# 06_-_POWER.net
KiCad netlist of a schematic drawn in Altium Designer
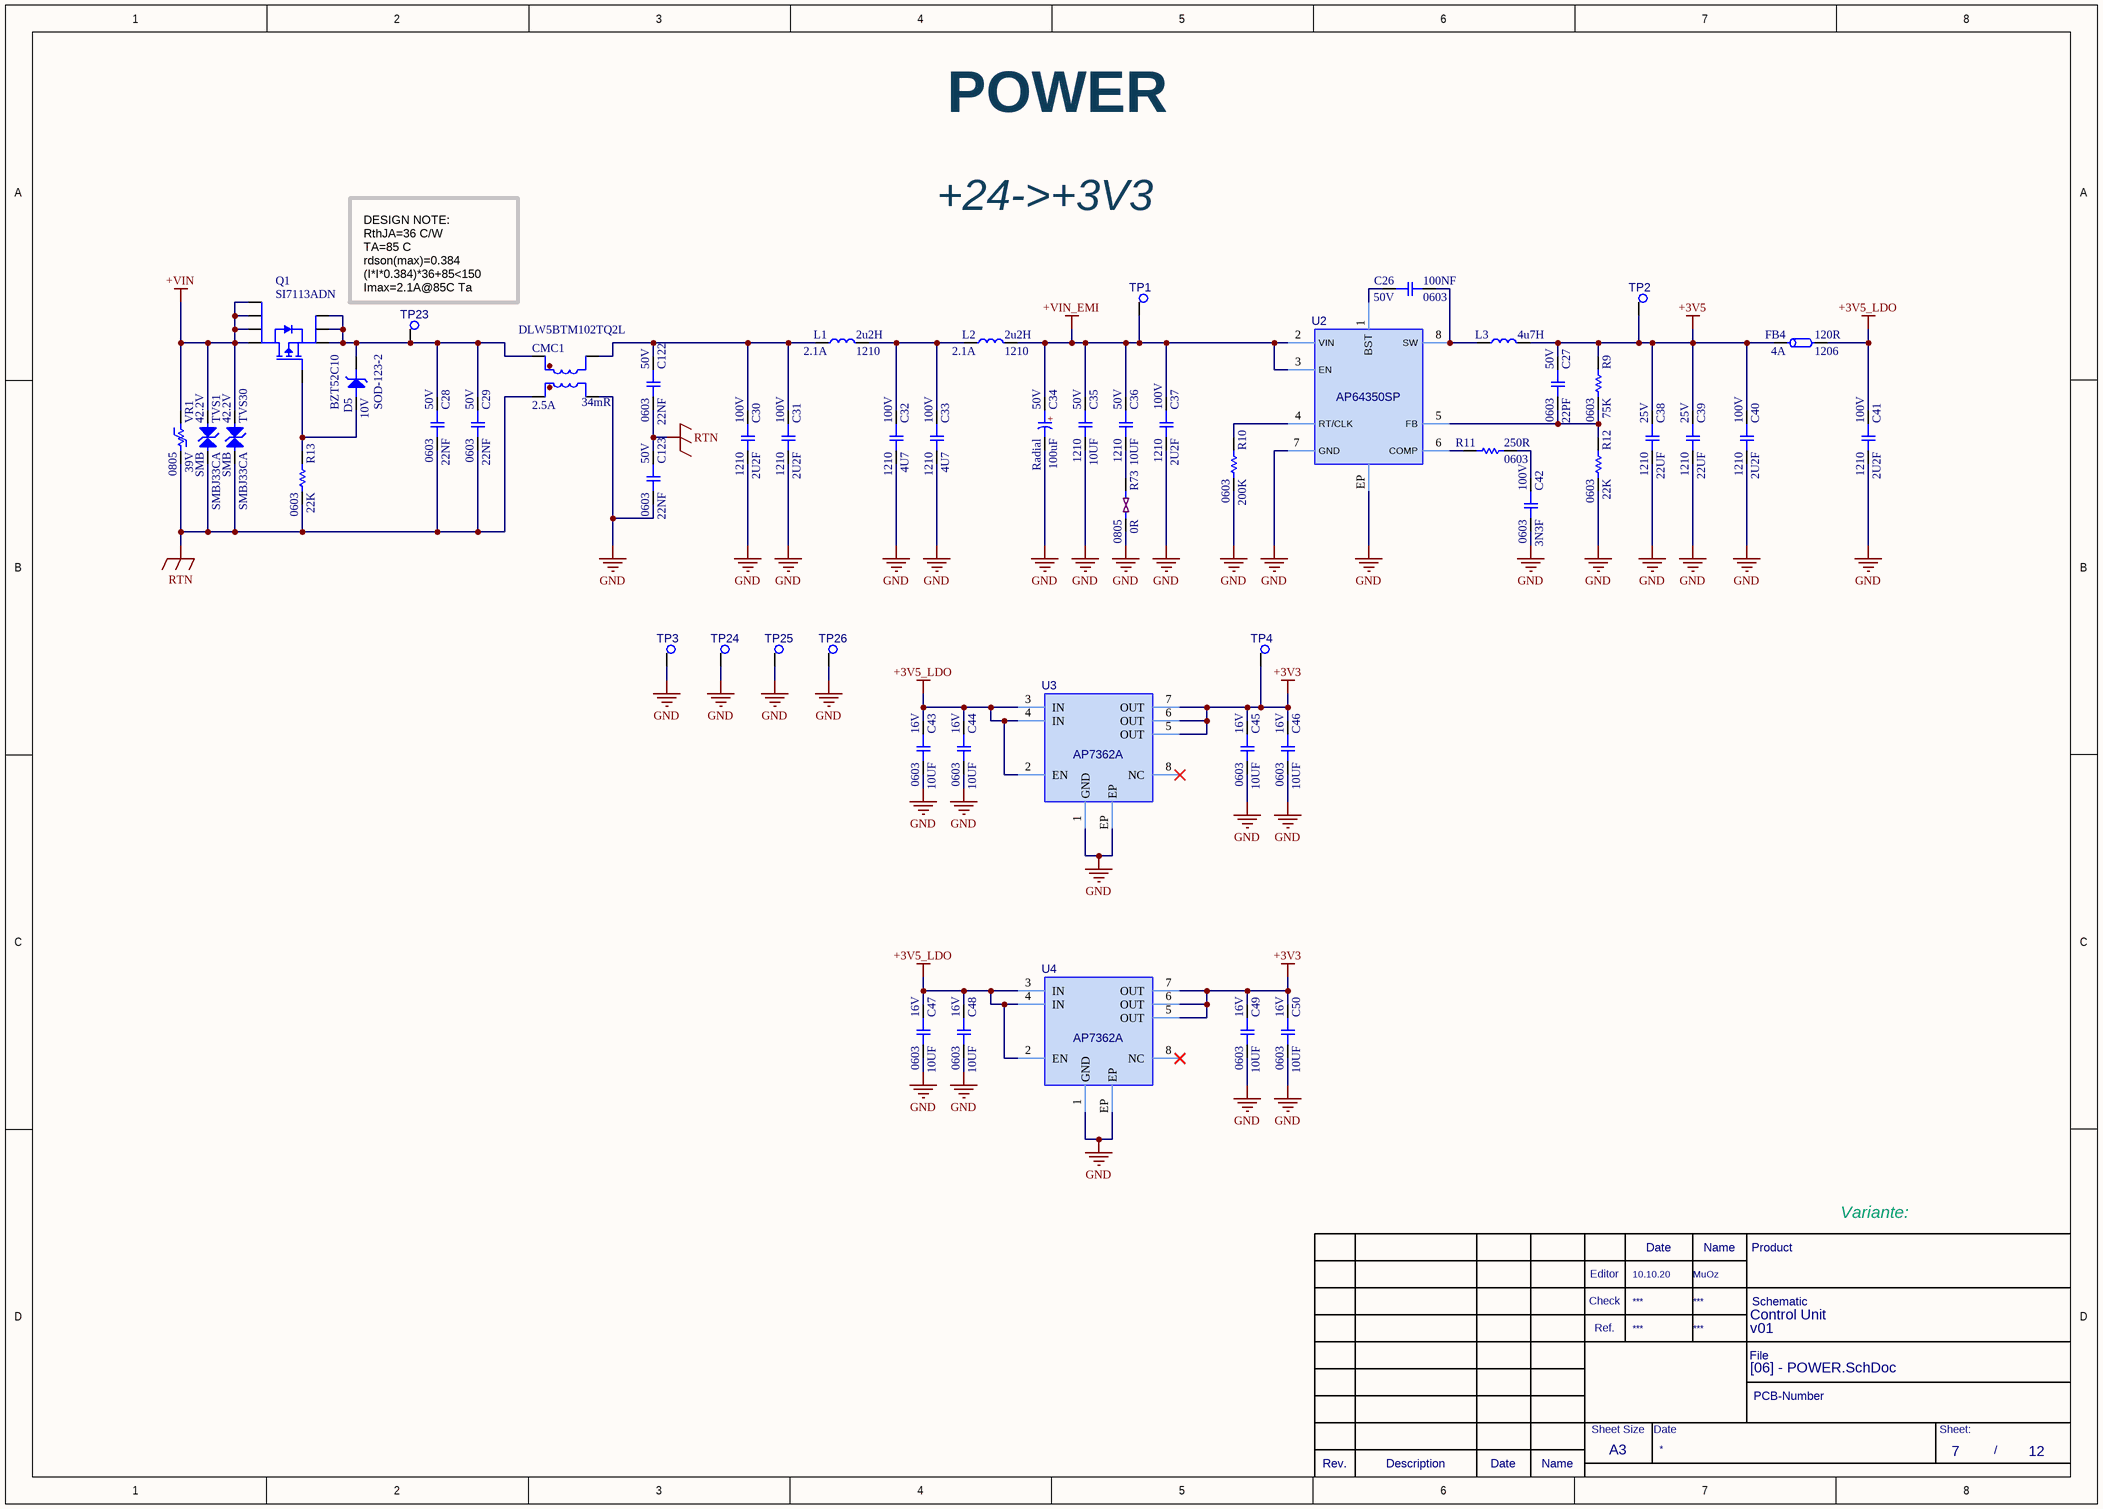
[diagram p0: [06] - POWER.SchDoc]

(export (version "E")
  (design (tool "Eeschema 10.0.6"))
  (components
    (comp (ref "C26")
      (value "100NF")
      (footprint "C-0603")
      (description "CAP CER 0.1UF 50V X7R 0603")
      (fields
        (field (name "MANUFACTURER") "TDK")
        (field (name "MANUFACTURER PART NUMBER") "C1608X7R1H104K080AA")
        (field (name "VOLTAGE RATING") "50V")
        (field (name "CASE CODE (IMPERIAL)") "0603")
        (field (name ".CREATOR") "F:TALI")
      )
      (libsource (lib "BARKO_SCHLIB") (part "C-100NF-0603"))
    )
    (comp (ref "C27")
      (value "22PF")
      (footprint "C-0603")
      (description "CAP CER 22PF 50V C0G/NP0 0603")
      (fields
        (field (name "MANUFACTURER") "Samsung")
        (field (name "MANUFACTURER PART NUMBER") "CL10C220JB8NNNC")
        (field (name "VOLTAGE RATING") "50V")
        (field (name "CASE/PACKAGE") "0603")
        (field (name ".CREATOR") "F:TALI")
      )
      (libsource (lib "BARKO_SCHLIB") (part "C-22PF-0603"))
    )
    (comp (ref "C28")
      (value "22NF")
      (footprint "C-0603")
      (description "CAP CER 0.022UF 50V X7R 0603L")
      (fields
        (field (name "MANUFACTURER") "Yageo")
        (field (name "MANUFACTURER PART NUMBER") "CC0603KRX7R9BB223")
        (field (name "VOLTAGE RATING") "50V")
        (field (name "CASE/PACKAGE") "0603")
        (field (name ".CREATOR") "M.OZKAN")
      )
      (libsource (lib "BARKO_SCHLIB") (part "C-22NF-0603"))
    )
    (comp (ref "C29")
      (value "22NF")
      (footprint "C-0603")
      (description "CAP CER 0.022UF 50V X7R 0603L")
      (fields
        (field (name "MANUFACTURER") "Yageo")
        (field (name "MANUFACTURER PART NUMBER") "CC0603KRX7R9BB223")
        (field (name "CASE/PACKAGE") "0603")
        (field (name "VOLTAGE") "50V")
        (field (name ".CREATOR") "M.OZKAN")
      )
      (libsource (lib "BARKO_SCHLIB") (part "C-22NF-0603"))
    )
    (comp (ref "C30")
      (value "2U2F")
      (footprint "C-1210")
      (description "CAP CER 2.2UF 100V X7R 1210")
      (fields
        (field (name "MANUFACTURER") "Samsung")
        (field (name "MANUFACTURER PART NUMBER") "CL32B225KCJSNNE")
        (field (name "VOLTAGE") "100V")
        (field (name "CASE/PACKAGE") "1210")
        (field (name ".CREATOR") "F:TALI")
      )
      (libsource (lib "BARKO_SCHLIB") (part "C-2U2F-1210"))
    )
    (comp (ref "C31")
      (value "2U2F")
      (footprint "C-1210")
      (description "CAP CER 2.2UF 100V X7R 1210")
      (fields
        (field (name "MANUFACTURER") "Samsung")
        (field (name "MANUFACTURER PART NUMBER") "CL32B225KCJSNNE")
        (field (name "VOLTAGE") "100V")
        (field (name "CASE/PACKAGE") "1210")
        (field (name ".CREATOR") "F:TALI")
      )
      (libsource (lib "BARKO_SCHLIB") (part "C-2U2F-1210"))
    )
    (comp (ref "C32")
      (value "4U7")
      (footprint "C-1210")
      (description "CAP CER 4.7UF 100V X7S 1210")
      (fields
        (field (name "MANUFACTURER") "Taiyo Yuden")
        (field (name "MANUFACTURER PART NUMBER") "HMK325C7475KM-PE")
        (field (name "CASE/PACKAGE") "1210")
        (field (name "VOLTAGE RATING") "100V")
      )
      (libsource (lib "BARKO_SCHLIB") (part "C-4U7-1210-100V"))
    )
    (comp (ref "C33")
      (value "4U7")
      (footprint "C-1210")
      (description "CAP CER 4.7UF 100V X7S 1210")
      (fields
        (field (name "MANUFACTURER") "Taiyo Yuden")
        (field (name "MANUFACTURER PART NUMBER") "HMK325C7475KM-PE")
        (field (name "CASE/PACKAGE") "1210")
        (field (name "VOLTAGE RATING") "100V")
      )
      (libsource (lib "BARKO_SCHLIB") (part "C-4U7-1210-100V"))
    )
    (comp (ref "C34")
      (value "100UF")
      (footprint "C-E-8.3x8.3x10.2")
      (description "CAP ALUM 100UF 20% 50V SMD")
      (fields
        (field (name "MANUFACTURER") "Nichicon")
        (field (name "MANUFACTURER PART NUMBER") "UUD1H101MNL1GS")
        (field (name "CASE/PACKAGE") "Radial")
        (field (name "VOLTAGE RATING (DC)") "50V")
        (field (name "CAPACITANCE") "100uF")
        (field (name ".CREATOR") "M.OZKAN")
      )
      (libsource (lib "BARKO_SCHLIB") (part "C-100UF-SMD"))
    )
    (comp (ref "C35")
      (value "10UF")
      (footprint "C-1210")
      (description "CAP CER 10UF 50V X7R 1210")
      (fields
        (field (name "MANUFACTURER") "Samsung")
        (field (name "MANUFACTURER PART NUMBER") "CL32B106KBJNNNE")
        (field (name "VOLTAGE RATING") "50V")
        (field (name "CASE/PACKAGE") "1210")
        (field (name ".CREATOR") "M.OZKAN")
      )
      (libsource (lib "BARKO_SCHLIB") (part "C-10UF-1210"))
    )
    (comp (ref "C36")
      (value "10UF")
      (footprint "C-1210")
      (description "CAP CER 10UF 50V X7R 1210")
      (fields
        (field (name "MANUFACTURER") "Samsung")
        (field (name "MANUFACTURER PART NUMBER") "CL32B106KBJNNNE")
        (field (name "VOLTAGE RATING") "50V")
        (field (name "CASE/PACKAGE") "1210")
        (field (name ".CREATOR") "M.OZKAN")
      )
      (libsource (lib "BARKO_SCHLIB") (part "C-10UF-1210"))
    )
    (comp (ref "C37")
      (value "2U2F")
      (footprint "C-1210")
      (description "CAP CER 2.2UF 100V X7R 1210")
      (fields
        (field (name "MANUFACTURER") "Samsung")
        (field (name "MANUFACTURER PART NUMBER") "CL32B225KCJSNNE")
        (field (name "VOLTAGE") "100V")
        (field (name "CASE/PACKAGE") "1210")
        (field (name ".CREATOR") "F:TALI")
      )
      (libsource (lib "BARKO_SCHLIB") (part "C-2U2F-1210"))
    )
    (comp (ref "C38")
      (value "22UF")
      (footprint "C-1210")
      (description "CAP CER 22UF 25V X7R 1210")
      (fields
        (field (name "MANUFACTURER") "Samsung")
        (field (name "MANUFACTURER PART NUMBER") "CL32B226KAJNNNE")
        (field (name "VOLTAGE RATING") "25V")
        (field (name "CASE CODE (IMPERIAL)") "1210")
        (field (name ".CREATOR") "F:TALI")
      )
      (libsource (lib "BARKO_SCHLIB") (part "C-22UF-1210"))
    )
    (comp (ref "C39")
      (value "22UF")
      (footprint "C-1210")
      (description "CAP CER 22UF 25V X7R 1210")
      (fields
        (field (name "MANUFACTURER") "Samsung")
        (field (name "MANUFACTURER PART NUMBER") "CL32B226KAJNNNE")
        (field (name "VOLTAGE RATING") "25V")
        (field (name "CASE CODE (IMPERIAL)") "1210")
        (field (name ".CREATOR") "F:TALI")
      )
      (libsource (lib "BARKO_SCHLIB") (part "C-22UF-1210"))
    )
    (comp (ref "C40")
      (value "2U2F")
      (footprint "C-1210")
      (description "CAP CER 2.2UF 100V X7R 1210")
      (fields
        (field (name "MANUFACTURER") "Samsung")
        (field (name "MANUFACTURER PART NUMBER") "CL32B225KCJSNNE")
        (field (name "VOLTAGE") "100V")
        (field (name "CASE/PACKAGE") "1210")
        (field (name ".CREATOR") "F:TALI")
      )
      (libsource (lib "BARKO_SCHLIB") (part "C-2U2F-1210"))
    )
    (comp (ref "C41")
      (value "2U2F")
      (footprint "C-1210")
      (description "CAP CER 2.2UF 100V X7R 1210")
      (fields
        (field (name "MANUFACTURER") "Samsung")
        (field (name "MANUFACTURER PART NUMBER") "CL32B225KCJSNNE")
        (field (name "VOLTAGE") "100V")
        (field (name "CASE/PACKAGE") "1210")
        (field (name ".CREATOR") "F:TALI")
      )
      (libsource (lib "BARKO_SCHLIB") (part "C-2U2F-1210"))
    )
    (comp (ref "C42")
      (value "3N3F")
      (footprint "C-0603")
      (description "CAP CER 3300PF 100V X7R 0603")
      (fields
        (field (name "MANUFACTURER PART NUMBER") "CGA3E2X7R2A332K080AA")
        (field (name "TOLERANCE") "10%")
        (field (name "VOLTAGE RATING") "100V")
        (field (name "CASE/PACKAGE") "0603")
        (field (name ".CREATOR") "F:TALI")
      )
      (libsource (lib "BARKO_SCHLIB") (part "C-3N3F-0603"))
    )
    (comp (ref "C43")
      (value "10UF")
      (footprint "C-0603")
      (description "CAP CER 10UF 16V X6S 0603")
      (fields
        (field (name "MANUFACTURER") "Murata")
        (field (name "MANUFACTURER PART NUMBER") "GRM188C81C106MA73D")
        (field (name "VOLTAGE RATING") "16V")
        (field (name "CASE/PACKAGE") "0603")
        (field (name ".CREATOR") "M.OZKAN")
      )
      (libsource (lib "BARKO_SCHLIB") (part "C-10UF-0603"))
    )
    (comp (ref "C44")
      (value "10UF")
      (footprint "C-0603")
      (description "CAP CER 10UF 16V X6S 0603")
      (fields
        (field (name "MANUFACTURER") "Murata")
        (field (name "MANUFACTURER PART NUMBER") "GRM188C81C106MA73D")
        (field (name "VOLTAGE RATING") "16V")
        (field (name "CASE/PACKAGE") "0603")
        (field (name ".CREATOR") "M.OZKAN")
      )
      (libsource (lib "BARKO_SCHLIB") (part "C-10UF-0603"))
    )
    (comp (ref "C45")
      (value "10UF")
      (footprint "C-0603")
      (description "CAP CER 10UF 16V X6S 0603")
      (fields
        (field (name "MANUFACTURER") "Murata")
        (field (name "MANUFACTURER PART NUMBER") "GRM188C81C106MA73D")
        (field (name "VOLTAGE RATING") "16V")
        (field (name "CASE/PACKAGE") "0603")
        (field (name ".CREATOR") "M.OZKAN")
      )
      (libsource (lib "BARKO_SCHLIB") (part "C-10UF-0603"))
    )
    (comp (ref "C46")
      (value "10UF")
      (footprint "C-0603")
      (description "CAP CER 10UF 16V X6S 0603")
      (fields
        (field (name "MANUFACTURER") "Murata")
        (field (name "MANUFACTURER PART NUMBER") "GRM188C81C106MA73D")
        (field (name "VOLTAGE RATING") "16V")
        (field (name "CASE/PACKAGE") "0603")
        (field (name ".CREATOR") "M.OZKAN")
      )
      (libsource (lib "BARKO_SCHLIB") (part "C-10UF-0603"))
    )
    (comp (ref "C47")
      (value "10UF")
      (footprint "C-0603")
      (description "CAP CER 10UF 16V X6S 0603")
      (fields
        (field (name "MANUFACTURER") "Murata")
        (field (name "MANUFACTURER PART NUMBER") "GRM188C81C106MA73D")
        (field (name "VOLTAGE RATING") "16V")
        (field (name "CASE/PACKAGE") "0603")
        (field (name ".CREATOR") "M.OZKAN")
      )
      (libsource (lib "BARKO_SCHLIB") (part "C-10UF-0603"))
    )
    (comp (ref "C48")
      (value "10UF")
      (footprint "C-0603")
      (description "CAP CER 10UF 16V X6S 0603")
      (fields
        (field (name "MANUFACTURER") "Murata")
        (field (name "MANUFACTURER PART NUMBER") "GRM188C81C106MA73D")
        (field (name "VOLTAGE RATING") "16V")
        (field (name "CASE/PACKAGE") "0603")
        (field (name ".CREATOR") "M.OZKAN")
      )
      (libsource (lib "BARKO_SCHLIB") (part "C-10UF-0603"))
    )
    (comp (ref "C49")
      (value "10UF")
      (footprint "C-0603")
      (description "CAP CER 10UF 16V X6S 0603")
      (fields
        (field (name "MANUFACTURER") "Murata")
        (field (name "MANUFACTURER PART NUMBER") "GRM188C81C106MA73D")
        (field (name "VOLTAGE RATING") "16V")
        (field (name "CASE/PACKAGE") "0603")
        (field (name ".CREATOR") "M.OZKAN")
      )
      (libsource (lib "BARKO_SCHLIB") (part "C-10UF-0603"))
    )
    (comp (ref "C50")
      (value "10UF")
      (footprint "C-0603")
      (description "CAP CER 10UF 16V X6S 0603")
      (fields
        (field (name "MANUFACTURER") "Murata")
        (field (name "MANUFACTURER PART NUMBER") "GRM188C81C106MA73D")
        (field (name "VOLTAGE RATING") "16V")
        (field (name "CASE/PACKAGE") "0603")
        (field (name ".CREATOR") "M.OZKAN")
      )
      (libsource (lib "BARKO_SCHLIB") (part "C-10UF-0603"))
    )
    (comp (ref "C122")
      (value "22NF")
      (footprint "C-0603")
      (description "CAP CER 0.022UF 50V X7R 0603L")
      (fields
        (field (name "MANUFACTURER") "Yageo")
        (field (name "MANUFACTURER PART NUMBER") "CC0603KRX7R9BB223")
        (field (name "CASE/PACKAGE") "0603")
        (field (name "VOLTAGE") "50V")
        (field (name ".CREATOR") "M.OZKAN")
      )
      (libsource (lib "BARKO_SCHLIB") (part "C-22NF-0603"))
    )
    (comp (ref "C123")
      (value "22NF")
      (footprint "C-0603")
      (description "CAP CER 0.022UF 50V X7R 0603L")
      (fields
        (field (name "MANUFACTURER") "Yageo")
        (field (name "MANUFACTURER PART NUMBER") "CC0603KRX7R9BB223")
        (field (name "CASE/PACKAGE") "0603")
        (field (name "VOLTAGE") "50V")
        (field (name ".CREATOR") "M.OZKAN")
      )
      (libsource (lib "BARKO_SCHLIB") (part "C-22NF-0603"))
    )
    (comp (ref "CMC1")
      (value "DLW5BTM102TQ2L")
      (footprint "CMC-DLW5BTM")
      (description "CMC 2.5A 2LN 1 KOHM SMD")
      (fields
        (field (name "MANUFACTURER") "Murata")
        (field (name "DC RESISTANCE (DCR)") "34mR")
        (field (name "MAX CURRENT RATING") "2.5A")
      )
      (libsource (lib "BARKO_SCHLIB") (part "CMC-DLW5BTM102TQ2L"))
    )
    (comp (ref "D5")
      (value "BZT52C10")
      (footprint "D-SOD123")
      (description "DIODE ZENER 10V 500MW SOD123")
      (fields
        (field (name "MANUFACTURER") "Diodes")
        (field (name "MANUFACTURER PART NUMBER") "BZT52C10-7-F")
        (field (name "ZENER VOLTAGE") "10V")
        (field (name "CASE/PACKAGE") "SOD-123-2")
        (field (name ".CREATOR") "F:TALI")
      )
      (libsource (lib "BARKO_SCHLIB") (part "D-BZT52C10-SOD123"))
    )
    (comp (ref "FB4")
      (value "120R")
      (footprint "FB-1206")
      (description "FERRITE BEAD 120 OHM 1206 1LN")
      (fields
        (field (name "MANUFACTURER") "Laird")
        (field (name "MANUFACTURER PART NUMBER") "HI1206P121R-10")
        (field (name "CURRENT RATING") "4A")
        (field (name "CASE CODE (IMPERIAL)") "1206")
        (field (name ".CREATOR") "F:TALI")
      )
      (libsource (lib "BARKO_SCHLIB") (part "FB-120R-1206"))
    )
    (comp (ref "L1")
      (value "2u2H")
      (footprint "WE-PMCI_1210_H1")
      (description "FIXED IND 2.2UH 2.1A 106 MOHM")
      (fields
        (field (name "MANUFACTURER") "Wurth Electronics")
        (field (name "MANUFACTURER PART NUMBER") "74479299222")
        (field (name "CASE/PACKAGE") "1210")
        (field (name "CURRENT RATING") "2.1A")
      )
      (libsource (lib "BARKO_SCHLIB") (part "L-2u2H-74479299222"))
    )
    (comp (ref "L2")
      (value "2u2H")
      (footprint "WE-PMCI_1210_H1")
      (description "FIXED IND 2.2UH 2.1A 106 MOHM")
      (fields
        (field (name "MANUFACTURER") "Wurth Electronics")
        (field (name "MANUFACTURER PART NUMBER") "74479299222")
        (field (name "CASE/PACKAGE") "1210")
        (field (name "CURRENT RATING") "2.1A")
      )
      (libsource (lib "BARKO_SCHLIB") (part "L-2u2H-74479299222"))
    )
    (comp (ref "L3")
      (value "4u7H")
      (footprint "WE-MAPI_5030")
      (description "FIXED IND 4.7UH 5.5A 34.5MOHM")
      (fields
        (field (name "MANUFACTURER PART NUMBER") "74438367047")
        (field (name "MANUFACTURER") "Wurth Electronics")
      )
      (libsource (lib "BARKO_SCHLIB") (part "L-4u7H-74438367047"))
    )
    (comp (ref "Q1")
      (value "SI7113ADN")
      (footprint "PowerPAK 1212-8")
      (description "MOSFET P-CH 100V 10.8A 1212-8")
      (fields
        (field (name "MANUFACTURER") "Vishay")
        (field (name "MANUFACTURER PART NUMBER") "SI7113ADN-T1-GE3")
        (field (name ".CREATOR") "M.OZKAN")
      )
      (libsource (lib "BARKO_SCHLIB") (part "Q-SI7113ADN-T1-GE3"))
    )
    (comp (ref "R9")
      (value "75K")
      (footprint "R-0603")
      (description "RES 100K OHM 1% 1/10W 0603")
      (fields
        (field (name "MANUFACTURER") "Stackpole Electronics")
        (field (name "MANUFACTURER PART NUMBER") "RMCF0603FT100K")
        (field (name "CASE/PACKAGE") "0603")
        (field (name ".CREATOR") "M.OZKAN")
      )
      (libsource (lib "BARKO_SCHLIB") (part "R-75K-0603"))
    )
    (comp (ref "R10")
      (value "200K")
      (footprint "R-0603")
      (description "RES 200K OHM 1% 1/10W 0603")
      (fields
        (field (name "MANUFACTURER PART NUMBER") "RMCF0603FT200K")
        (field (name "TOLERANCE") "1%")
        (field (name "CASE/PACKAGE") "0603")
      )
      (libsource (lib "BARKO_SCHLIB") (part "R-200K-0603"))
    )
    (comp (ref "R11")
      (value "250R")
      (footprint "R-0603")
      (description "RES 250 OHM 0.01% 1/10W 0603")
      (fields
        (field (name "MANUFACTURER PART NUMBER") "RNCF0603TKY250R")
        (field (name "TOLERANCE") "0.01%")
        (field (name "CASE/PACKAGE") "0603")
      )
      (libsource (lib "BARKO_SCHLIB") (part "R-250R-0603"))
    )
    (comp (ref "R12")
      (value "22K")
      (footprint "R-0603")
      (description "RES SMD 22K OHM 1% 1/8W 0603")
      (fields
        (field (name "MANUFACTURER") "Vishay Beyschlag")
        (field (name "MANUFACTURER PART NUMBER") "MCT06030C2202FP500")
        (field (name "CASE CODE (IMPERIAL)") "0603")
        (field (name ".CREATOR") "F:TALI")
      )
      (libsource (lib "BARKO_SCHLIB") (part "R-22K-0603"))
    )
    (comp (ref "R13")
      (value "22K")
      (footprint "R-0603")
      (description "RES SMD 22K OHM 1% 1/8W 0603")
      (fields
        (field (name "MANUFACTURER PART NUMBER") "MCT06030C2202FP500")
        (field (name "TOLERANCE") "1%")
        (field (name "CASE/PACKAGE") "0603")
        (field (name ".CREATOR") "F:TALI")
      )
      (libsource (lib "BARKO_SCHLIB") (part "R-22K-0603"))
    )
    (comp (ref "R73")
      (value "0R")
      (footprint "JMP-0805")
      (description "RES SMD 0 OHM JUMPER 1/8W 0805")
      (fields
        (field (name "MANUFACTURER") "Yageo")
        (field (name "MANUFACTURER PART NUMBER") "RC0805JR-070RL")
        (field (name "CASE CODE (IMPERIAL)") "0805")
        (field (name ".CREATOR") "F:TALI")
      )
      (libsource (lib "BARKO_SCHLIB") (part "R-0R-0805"))
    )
    (comp (ref "TP1")
      (value "MECH-TESTPOINT")
      (footprint "PAD TH")
      (fields (field (name ".CREATOR") "F:TALI"))
      (libsource (lib "BARKO_SCHLIB") (part "MECH-TESTPOINT"))
    )
    (comp (ref "TP2")
      (value "MECH-TESTPOINT")
      (footprint "PAD TH")
      (fields (field (name ".CREATOR") "F:TALI"))
      (libsource (lib "BARKO_SCHLIB") (part "MECH-TESTPOINT"))
    )
    (comp (ref "TP3")
      (value "MECH-TESTPOINT")
      (footprint "PAD TH")
      (fields (field (name ".CREATOR") "F:TALI"))
      (libsource (lib "BARKO_SCHLIB") (part "MECH-TESTPOINT"))
    )
    (comp (ref "TP4")
      (value "MECH-TESTPOINT")
      (footprint "PAD TH")
      (fields (field (name ".CREATOR") "F:TALI"))
      (libsource (lib "BARKO_SCHLIB") (part "MECH-TESTPOINT"))
    )
    (comp (ref "TP23")
      (value "MECH-TESTPOINT")
      (footprint "MECH-TESTPOINT")
      (fields (field (name ".CREATOR") "F:TALI"))
      (libsource (lib "BARKO_SCHLIB") (part "MECH-TESTPOINT"))
    )
    (comp (ref "TP24")
      (value "MECH-TESTPOINT")
      (footprint "PAD TH")
      (fields (field (name ".CREATOR") "F:TALI"))
      (libsource (lib "BARKO_SCHLIB") (part "MECH-TESTPOINT"))
    )
    (comp (ref "TP25")
      (value "MECH-TESTPOINT")
      (footprint "PAD TH")
      (fields (field (name ".CREATOR") "F:TALI"))
      (libsource (lib "BARKO_SCHLIB") (part "MECH-TESTPOINT"))
    )
    (comp (ref "TP26")
      (value "MECH-TESTPOINT")
      (footprint "PAD TH")
      (fields (field (name ".CREATOR") "F:TALI"))
      (libsource (lib "BARKO_SCHLIB") (part "MECH-TESTPOINT"))
    )
    (comp (ref "TVS1")
      (value "SMBJ33CA")
      (footprint "D-SMB-DO214AA-CA")
      (description "DIODE TVS 33VWM 53.3VC SMB")
      (fields
        (field (name "MANUFACTURER") "Bourns")
        (field (name "CASE/PACKAGE") "SMB")
        (field (name "BREAKDOWN VOLTAGE") "42.2V")
        (field (name ".CREATOR") "M.OZKAN")
      )
      (libsource (lib "BARKO_SCHLIB") (part "TVS-SMBJ33CA-SMB"))
    )
    (comp (ref "TVS30")
      (value "SMBJ33CA")
      (footprint "D-SMB-DO214AA-CA")
      (description "DIODE TVS 33VWM 53.3VC SMB")
      (fields
        (field (name "MANUFACTURER") "Bourns")
        (field (name "CASE/PACKAGE") "SMB")
        (field (name "BREAKDOWN VOLTAGE") "42.2V")
        (field (name ".CREATOR") "M.OZKAN")
      )
      (libsource (lib "BARKO_SCHLIB") (part "TVS-SMBJ33CA-SMB"))
    )
    (comp (ref "U2")
      (value "AP64350SP")
      (footprint "SOIC8-EP")
      (description "DCDC CONV HV BUCK SO-8EP")
      (fields (field (name "MANUFACTURER PART NUMBER") "AP64350SP-13"))
      (libsource (lib "SCHLIB") (part "IC-AP64350SP-13"))
    )
    (comp (ref "U3")
      (value "AP7362A")
      (footprint "SOIC8-EP")
      (description "IC REG LINEAR 3.3V 1.5A 8SO")
      (fields
        (field (name "MANUFACTURER") "Diodes")
        (field (name "MANUFACTURER PART NUMBER") "AP7362A-33SP-13")
      )
      (libsource (lib "SCHLIB") (part "IC-AP7362A-33SP-13"))
    )
    (comp (ref "U4")
      (value "AP7362A")
      (footprint "SOIC8-EP")
      (description "IC REG LINEAR 3.3V 1.5A 8SO")
      (fields
        (field (name "MANUFACTURER") "Diodes")
        (field (name "MANUFACTURER PART NUMBER") "AP7362A-33SP-13")
      )
      (libsource (lib "SCHLIB") (part "IC-AP7362A-33SP-13"))
    )
    (comp (ref "VR1")
      (value "B72510E1250K62")
      (footprint "R-0805")
      (description "VARISTOR 39V 80A 0805")
      (fields
        (field (name "MANUFACTURER") "TDK EPCOS")
        (field (name "TOLERANCE") "10%")
        (field (name "VARISTOR VOLTAGE") "39V")
        (field (name "CASE CODE (IMPERIAL)") "0805")
        (field (name ".CREATOR") "F:TALI")
      )
      (libsource (lib "BARKO_SCHLIB") (part "VR-B72510E1250K62"))
    )
  )
  (nets
    (net (code "1") (name "+3V3") (class "Default")
      (node (ref "C45") (pin "1") (pinfunction "1_1") (pintype "passive"))
      (node (ref "C46") (pin "1") (pinfunction "1_1") (pintype "passive"))
      (node (ref "C49") (pin "1") (pinfunction "1_1") (pintype "passive"))
      (node (ref "C50") (pin "1") (pinfunction "1_1") (pintype "passive"))
      (node (ref "TP4") (pin "1") (pinfunction "1_1") (pintype "passive"))
      (node (ref "U3") (pin "5") (pinfunction "OUT_5") (pintype "passive"))
      (node (ref "U3") (pin "6") (pinfunction "OUT_6") (pintype "passive"))
      (node (ref "U3") (pin "7") (pinfunction "OUT_7") (pintype "passive"))
      (node (ref "U4") (pin "5") (pinfunction "OUT_5") (pintype "passive"))
      (node (ref "U4") (pin "6") (pinfunction "OUT_6") (pintype "passive"))
      (node (ref "U4") (pin "7") (pinfunction "OUT_7") (pintype "passive"))
    )
    (net (code "2") (name "+3V5") (class "Default")
      (node (ref "C27") (pin "1") (pinfunction "1_1") (pintype "passive"))
      (node (ref "C38") (pin "1") (pinfunction "1_1") (pintype "passive"))
      (node (ref "C39") (pin "1") (pinfunction "1_1") (pintype "passive"))
      (node (ref "C40") (pin "1") (pinfunction "1_1") (pintype "passive"))
      (node (ref "FB4") (pin "1") (pinfunction "1_1") (pintype "passive"))
      (node (ref "L3") (pin "2") (pinfunction "2_2") (pintype "passive"))
      (node (ref "R9") (pin "1") (pinfunction "1_1") (pintype "passive"))
      (node (ref "TP2") (pin "1") (pinfunction "1_1") (pintype "passive"))
    )
    (net (code "3") (name "+3V5_LDO") (class "Default")
      (node (ref "C41") (pin "1") (pinfunction "1_1") (pintype "passive"))
      (node (ref "C43") (pin "1") (pinfunction "1_1") (pintype "passive"))
      (node (ref "C44") (pin "1") (pinfunction "1_1") (pintype "passive"))
      (node (ref "C47") (pin "1") (pinfunction "1_1") (pintype "passive"))
      (node (ref "C48") (pin "1") (pinfunction "1_1") (pintype "passive"))
      (node (ref "FB4") (pin "2") (pinfunction "2_2") (pintype "passive"))
      (node (ref "U3") (pin "2") (pinfunction "EN_2") (pintype "passive"))
      (node (ref "U3") (pin "3") (pinfunction "IN_3") (pintype "passive"))
      (node (ref "U3") (pin "4") (pinfunction "IN_4") (pintype "passive"))
      (node (ref "U4") (pin "2") (pinfunction "EN_2") (pintype "passive"))
      (node (ref "U4") (pin "3") (pinfunction "IN_3") (pintype "passive"))
      (node (ref "U4") (pin "4") (pinfunction "IN_4") (pintype "passive"))
    )
    (net (code "4") (name "+VIN") (class "Default")
      (node (ref "Q1") (pin "5") (pinfunction "D_5") (pintype "passive"))
      (node (ref "Q1") (pin "6") (pinfunction "D_6") (pintype "passive"))
      (node (ref "Q1") (pin "7") (pinfunction "D_7") (pintype "passive"))
      (node (ref "Q1") (pin "8") (pinfunction "D_8") (pintype "passive"))
      (node (ref "TVS1") (pin "A") (pinfunction "I/O1_A") (pintype "passive"))
      (node (ref "TVS30") (pin "A") (pinfunction "I/O1_A") (pintype "passive"))
      (node (ref "VR1") (pin "1") (pinfunction "1_1") (pintype "passive"))
    )
    (net (code "5") (name "+VIN_EMI") (class "Default")
      (node (ref "C34") (pin "1") (pinfunction "1_1") (pintype "passive"))
      (node (ref "C35") (pin "1") (pinfunction "1_1") (pintype "passive"))
      (node (ref "C36") (pin "1") (pinfunction "1_1") (pintype "passive"))
      (node (ref "C37") (pin "1") (pinfunction "1_1") (pintype "passive"))
      (node (ref "L2") (pin "2") (pinfunction "2_2") (pintype "passive"))
      (node (ref "TP1") (pin "1") (pinfunction "1_1") (pintype "passive"))
      (node (ref "U2") (pin "2") (pinfunction "VIN_2") (pintype "passive"))
      (node (ref "U2") (pin "3") (pinfunction "EN_3") (pintype "passive"))
    )
    (net (code "6") (name "GND") (class "Default")
      (node (ref "C123") (pin "2") (pinfunction "2_2") (pintype "passive"))
      (node (ref "C30") (pin "2") (pinfunction "2_2") (pintype "passive"))
      (node (ref "C31") (pin "2") (pinfunction "2_2") (pintype "passive"))
      (node (ref "C32") (pin "2") (pinfunction "2_2") (pintype "passive"))
      (node (ref "C33") (pin "2") (pinfunction "2_2") (pintype "passive"))
      (node (ref "C34") (pin "2") (pinfunction "2_2") (pintype "passive"))
      (node (ref "C35") (pin "2") (pinfunction "2_2") (pintype "passive"))
      (node (ref "C37") (pin "2") (pinfunction "2_2") (pintype "passive"))
      (node (ref "C38") (pin "2") (pinfunction "2_2") (pintype "passive"))
      (node (ref "C39") (pin "2") (pinfunction "2_2") (pintype "passive"))
      (node (ref "C40") (pin "2") (pinfunction "2_2") (pintype "passive"))
      (node (ref "C41") (pin "2") (pinfunction "2_2") (pintype "passive"))
      (node (ref "C42") (pin "2") (pinfunction "2_2") (pintype "passive"))
      (node (ref "C43") (pin "2") (pinfunction "2_2") (pintype "passive"))
      (node (ref "C44") (pin "2") (pinfunction "2_2") (pintype "passive"))
      (node (ref "C45") (pin "2") (pinfunction "2_2") (pintype "passive"))
      (node (ref "C46") (pin "2") (pinfunction "2_2") (pintype "passive"))
      (node (ref "C47") (pin "2") (pinfunction "2_2") (pintype "passive"))
      (node (ref "C48") (pin "2") (pinfunction "2_2") (pintype "passive"))
      (node (ref "C49") (pin "2") (pinfunction "2_2") (pintype "passive"))
      (node (ref "C50") (pin "2") (pinfunction "2_2") (pintype "passive"))
      (node (ref "CMC1") (pin "2") (pinfunction "2_2") (pintype "passive"))
      (node (ref "R10") (pin "2") (pinfunction "2_2") (pintype "passive"))
      (node (ref "R12") (pin "2") (pinfunction "2_2") (pintype "passive"))
      (node (ref "R73") (pin "2") (pinfunction "2_2") (pintype "passive"))
      (node (ref "TP24") (pin "1") (pinfunction "1_1") (pintype "passive"))
      (node (ref "TP25") (pin "1") (pinfunction "1_1") (pintype "passive"))
      (node (ref "TP26") (pin "1") (pinfunction "1_1") (pintype "passive"))
      (node (ref "TP3") (pin "1") (pinfunction "1_1") (pintype "passive"))
      (node (ref "U2") (pin "7") (pinfunction "GND_7") (pintype "passive"))
      (node (ref "U2") (pin "EP") (pinfunction "GND_EP") (pintype "passive"))
      (node (ref "U3") (pin "1") (pinfunction "GND_1") (pintype "passive"))
      (node (ref "U3") (pin "EP") (pinfunction "EP_EP") (pintype "passive"))
      (node (ref "U4") (pin "1") (pinfunction "GND_1") (pintype "passive"))
      (node (ref "U4") (pin "EP") (pinfunction "EP_EP") (pintype "passive"))
    )
    (net (code "7") (name "Net-(C28-Pad1)") (class "Default")
      (node (ref "C28") (pin "1") (pinfunction "1_1") (pintype "passive"))
      (node (ref "C29") (pin "1") (pinfunction "1_1") (pintype "passive"))
      (node (ref "CMC1") (pin "4") (pinfunction "4_4") (pintype "passive"))
      (node (ref "D5") (pin "C") (pinfunction "C_C") (pintype "passive"))
      (node (ref "Q1") (pin "1") (pinfunction "S_1") (pintype "passive"))
      (node (ref "Q1") (pin "2") (pinfunction "S_2") (pintype "passive"))
      (node (ref "Q1") (pin "3") (pinfunction "S_3") (pintype "passive"))
      (node (ref "TP23") (pin "1") (pinfunction "1_1") (pintype "passive"))
    )
    (net (code "8") (name "Net-(C32-Pad1)") (class "Default")
      (node (ref "C32") (pin "1") (pinfunction "1_1") (pintype "passive"))
      (node (ref "C33") (pin "1") (pinfunction "1_1") (pintype "passive"))
      (node (ref "L1") (pin "2") (pinfunction "2_2") (pintype "passive"))
      (node (ref "L2") (pin "1") (pinfunction "1_1") (pintype "passive"))
    )
    (net (code "9") (name "Net-(C36-Pad2)") (class "Default")
      (node (ref "C36") (pin "2") (pinfunction "2_2") (pintype "passive"))
      (node (ref "R73") (pin "1") (pinfunction "1_1") (pintype "passive"))
    )
    (net (code "10") (name "Net-(C42-Pad1)") (class "Default")
      (node (ref "C42") (pin "1") (pinfunction "1_1") (pintype "passive"))
      (node (ref "R11") (pin "2") (pinfunction "2_2") (pintype "passive"))
    )
    (net (code "11") (name "Net-(C122-Pad1)") (class "Default")
      (node (ref "C122") (pin "1") (pinfunction "1_1") (pintype "passive"))
      (node (ref "C30") (pin "1") (pinfunction "1_1") (pintype "passive"))
      (node (ref "C31") (pin "1") (pinfunction "1_1") (pintype "passive"))
      (node (ref "CMC1") (pin "3") (pinfunction "3_3") (pintype "passive"))
      (node (ref "L1") (pin "1") (pinfunction "1_1") (pintype "passive"))
    )
    (net (code "12") (name "Net-(Q1-G)") (class "Default")
      (node (ref "D5") (pin "A") (pinfunction "A_A") (pintype "passive"))
      (node (ref "Q1") (pin "4") (pinfunction "G_4") (pintype "passive"))
      (node (ref "R13") (pin "1") (pinfunction "1_1") (pintype "passive"))
    )
    (net (code "13") (name "Net-(U2-BST)") (class "Default")
      (node (ref "C26") (pin "1") (pinfunction "1_1") (pintype "passive"))
      (node (ref "U2") (pin "1") (pinfunction "BST_1") (pintype "passive"))
    )
    (net (code "14") (name "Net-(U2-COMP)") (class "Default")
      (node (ref "R11") (pin "1") (pinfunction "1_1") (pintype "passive"))
      (node (ref "U2") (pin "6") (pinfunction "COMP_6") (pintype "passive"))
    )
    (net (code "15") (name "Net-(U2-FB)") (class "Default")
      (node (ref "C27") (pin "2") (pinfunction "2_2") (pintype "passive"))
      (node (ref "R12") (pin "1") (pinfunction "1_1") (pintype "passive"))
      (node (ref "R9") (pin "2") (pinfunction "2_2") (pintype "passive"))
      (node (ref "U2") (pin "5") (pinfunction "FB_5") (pintype "passive"))
    )
    (net (code "16") (name "Net-(U2-RT{slash}CLK)") (class "Default")
      (node (ref "R10") (pin "1") (pinfunction "1_1") (pintype "passive"))
      (node (ref "U2") (pin "4") (pinfunction "RT/CLK_4") (pintype "passive"))
    )
    (net (code "17") (name "Net-(U2-SW)") (class "Default")
      (node (ref "C26") (pin "2") (pinfunction "2_2") (pintype "passive"))
      (node (ref "L3") (pin "1") (pinfunction "1_1") (pintype "passive"))
      (node (ref "U2") (pin "8") (pinfunction "SW_8") (pintype "passive"))
    )
    (net (code "18") (name "RTN") (class "Default")
      (node (ref "C122") (pin "2") (pinfunction "2_2") (pintype "passive"))
      (node (ref "C123") (pin "1") (pinfunction "1_1") (pintype "passive"))
      (node (ref "C28") (pin "2") (pinfunction "2_2") (pintype "passive"))
      (node (ref "C29") (pin "2") (pinfunction "2_2") (pintype "passive"))
      (node (ref "CMC1") (pin "1") (pinfunction "1_1") (pintype "passive"))
      (node (ref "R13") (pin "2") (pinfunction "2_2") (pintype "passive"))
      (node (ref "TVS1") (pin "C") (pinfunction "I/O2_C") (pintype "passive"))
      (node (ref "TVS30") (pin "C") (pinfunction "I/O2_C") (pintype "passive"))
      (node (ref "VR1") (pin "2") (pinfunction "2_2") (pintype "passive"))
    )
    (net (code "19") (name "unconnected-(U3-NC-Pad8)") (class "Default")
      (node (ref "U3") (pin "8") (pinfunction "NC_8") (pintype "passive+no_connect"))
    )
    (net (code "20") (name "unconnected-(U4-NC-Pad8)") (class "Default")
      (node (ref "U4") (pin "8") (pinfunction "NC_8") (pintype "passive+no_connect"))
    )
  )
)
